# new-display.net
KiCad netlist of a schematic drawn in EAGLE
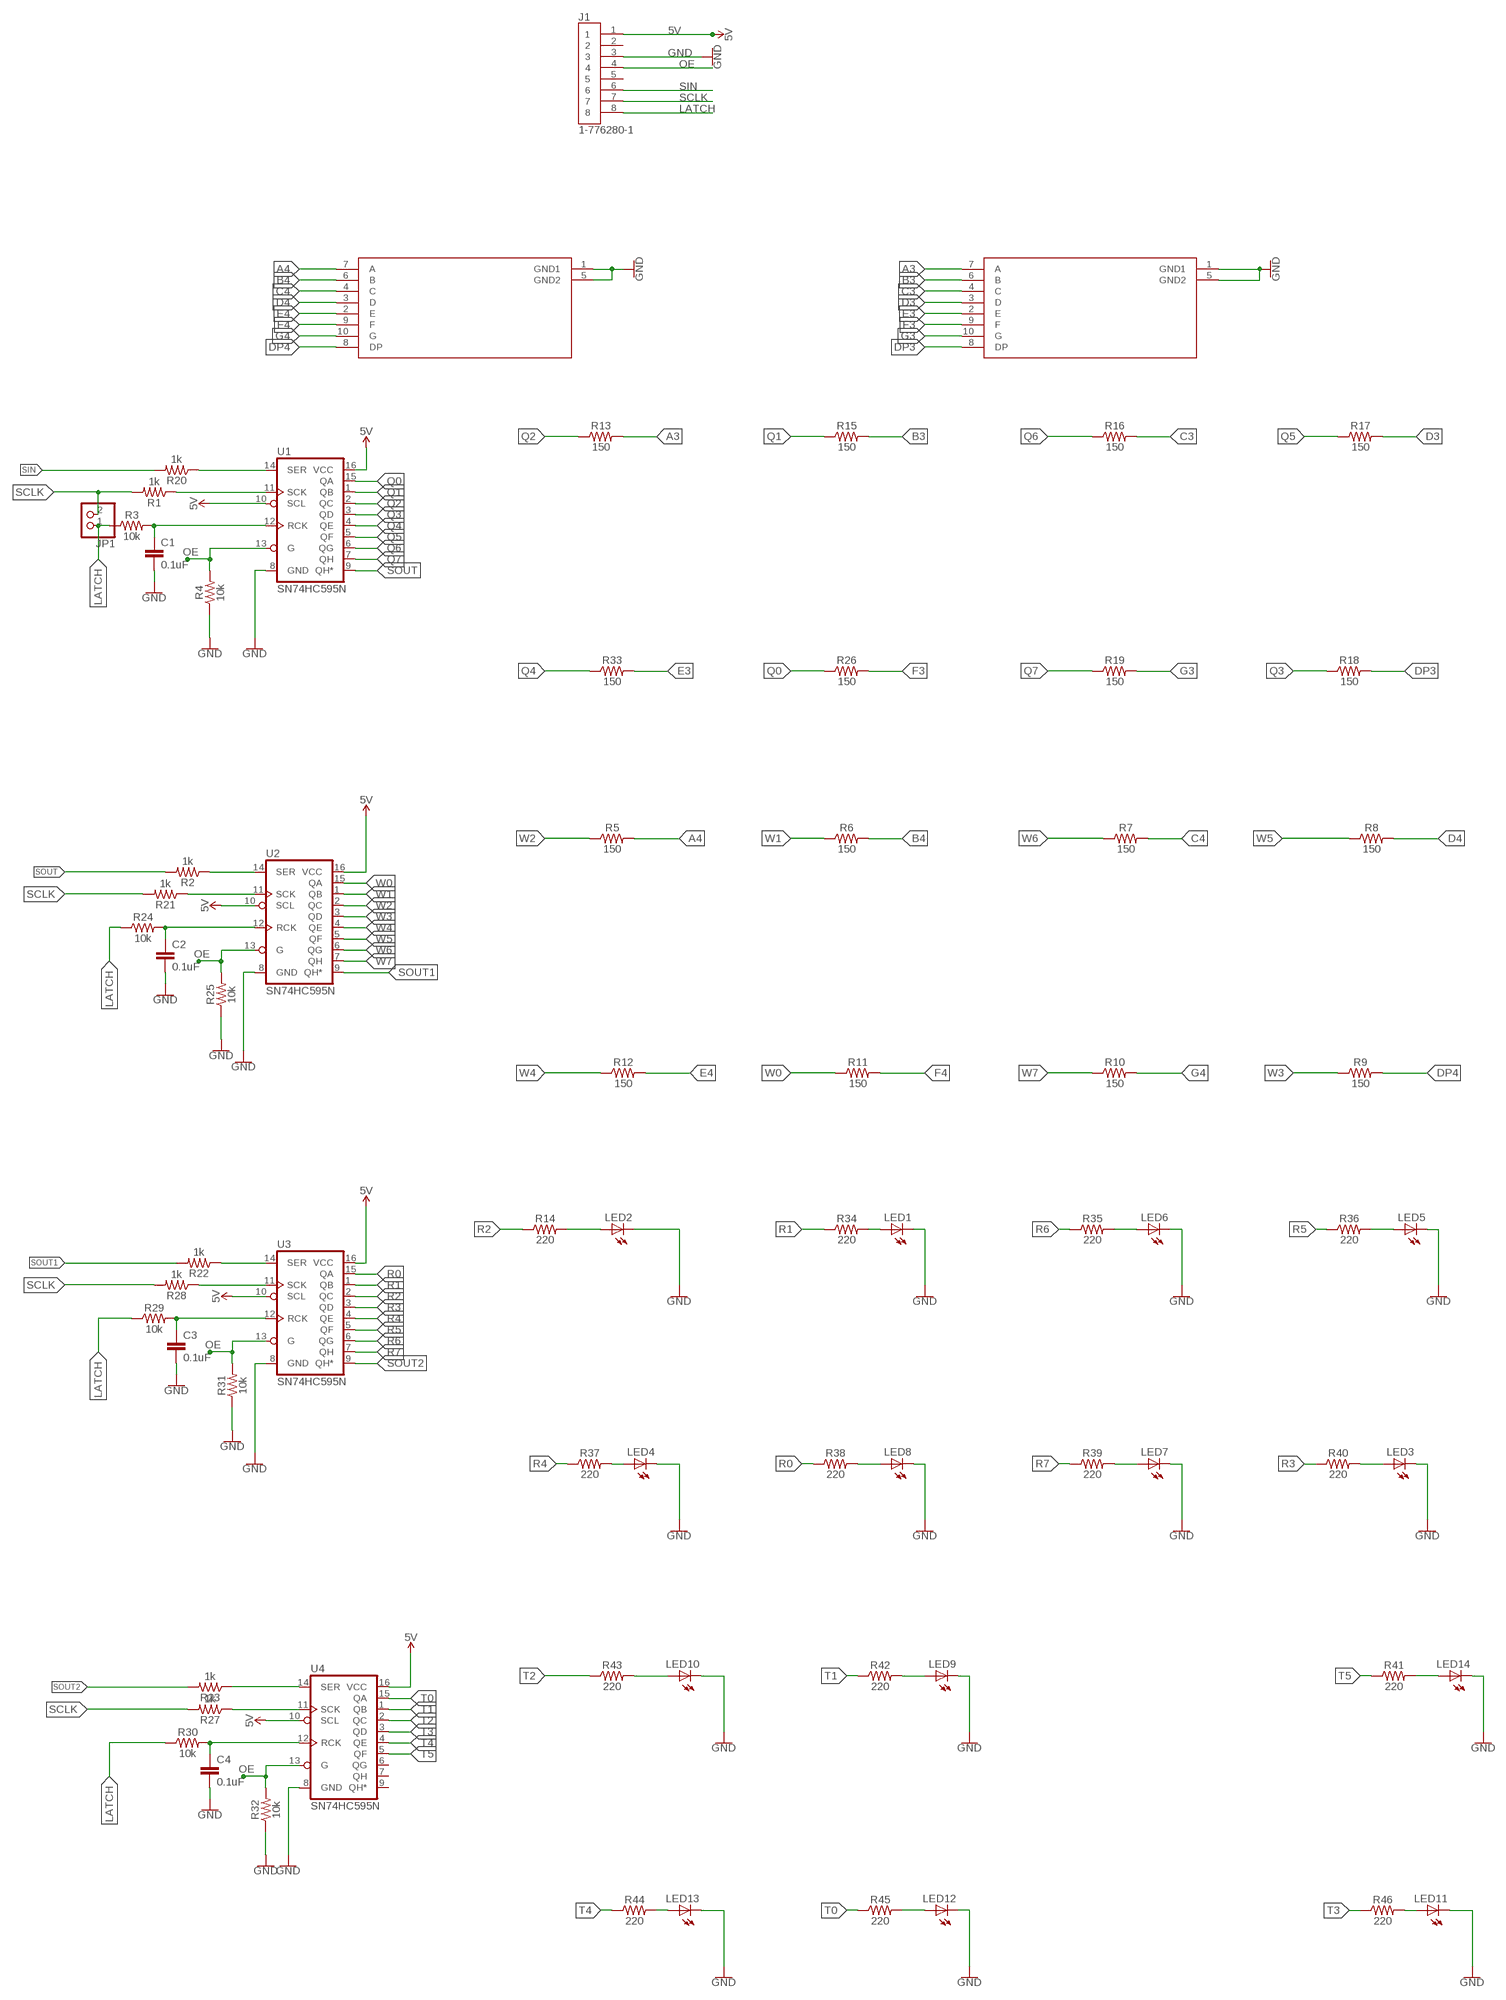
[diagram p0: schematic, sheet 1]

(export (version "E")
  (design (tool "Eeschema 10.0.6"))
  (components
    (comp (ref "C1")
      (value "0.1uF")
      (footprint "eagle-import:CAP-PTH-2.54")
      (libsource (lib "eagle-import") (part "22PF-PTH-2.54MM-200V-5%"))
    )
    (comp (ref "C2")
      (value "0.1uF")
      (footprint "eagle-import:CAP-PTH-2.54")
      (libsource (lib "eagle-import") (part "22PF-PTH-2.54MM-200V-5%"))
    )
    (comp (ref "C3")
      (value "0.1uF")
      (footprint "eagle-import:CAP-PTH-2.54")
      (libsource (lib "eagle-import") (part "22PF-PTH-2.54MM-200V-5%"))
    )
    (comp (ref "C4")
      (value "0.1uF")
      (footprint "eagle-import:CAP-PTH-2.54")
      (libsource (lib "eagle-import") (part "22PF-PTH-2.54MM-200V-5%"))
    )
    (comp (ref "J1")
      (value "1-776280-1")
      (footprint "eagle-import:TE_1-776280-1")
      (fields (field (name "MANUFACTURER") "TE Connectivity"))
      (libsource (lib "eagle-import") (part "1-776280-1"))
    )
    (comp (ref "JP1")
      (value "PINHD-1X2")
      (footprint "eagle-import:1X02")
      (libsource (lib "eagle-import") (part "PINHD-1X2"))
    )
    (comp (ref "LED1")
      (value "LED5MM")
      (footprint "eagle-import:LED5MM")
      (libsource (lib "eagle-import") (part "LED5MM"))
    )
    (comp (ref "LED2")
      (value "LED5MM")
      (footprint "eagle-import:LED5MM")
      (libsource (lib "eagle-import") (part "LED5MM"))
    )
    (comp (ref "LED3")
      (value "LED5MM")
      (footprint "eagle-import:LED5MM")
      (libsource (lib "eagle-import") (part "LED5MM"))
    )
    (comp (ref "LED4")
      (value "LED5MM")
      (footprint "eagle-import:LED5MM")
      (libsource (lib "eagle-import") (part "LED5MM"))
    )
    (comp (ref "LED5")
      (value "LED5MM")
      (footprint "eagle-import:LED5MM")
      (libsource (lib "eagle-import") (part "LED5MM"))
    )
    (comp (ref "LED6")
      (value "LED5MM")
      (footprint "eagle-import:LED5MM")
      (libsource (lib "eagle-import") (part "LED5MM"))
    )
    (comp (ref "LED7")
      (value "LED5MM")
      (footprint "eagle-import:LED5MM")
      (libsource (lib "eagle-import") (part "LED5MM"))
    )
    (comp (ref "LED8")
      (value "LED5MM")
      (footprint "eagle-import:LED5MM")
      (libsource (lib "eagle-import") (part "LED5MM"))
    )
    (comp (ref "LED9")
      (value "LED5MM")
      (footprint "eagle-import:LED5MM")
      (libsource (lib "eagle-import") (part "LED5MM"))
    )
    (comp (ref "LED10")
      (value "LED5MM")
      (footprint "eagle-import:LED5MM")
      (libsource (lib "eagle-import") (part "LED5MM"))
    )
    (comp (ref "LED11")
      (value "LED5MM")
      (footprint "eagle-import:LED5MM")
      (libsource (lib "eagle-import") (part "LED5MM"))
    )
    (comp (ref "LED12")
      (value "LED5MM")
      (footprint "eagle-import:LED5MM")
      (libsource (lib "eagle-import") (part "LED5MM"))
    )
    (comp (ref "LED13")
      (value "LED5MM")
      (footprint "eagle-import:LED5MM")
      (libsource (lib "eagle-import") (part "LED5MM"))
    )
    (comp (ref "LED14")
      (value "LED5MM")
      (footprint "eagle-import:LED5MM")
      (libsource (lib "eagle-import") (part "LED5MM"))
    )
    (comp (ref "R1")
      (value "1k")
      (footprint "eagle-import:AXIAL-0.3")
      (libsource (lib "eagle-import") (part "1KOHM-HORIZ-1/4W-5%"))
    )
    (comp (ref "R2")
      (value "1k")
      (footprint "eagle-import:AXIAL-0.3")
      (libsource (lib "eagle-import") (part "1KOHM-HORIZ-1/4W-5%"))
    )
    (comp (ref "R3")
      (value "10k")
      (footprint "eagle-import:AXIAL-0.3")
      (libsource (lib "eagle-import") (part "10KOHM-HORIZ-1/4W-5%"))
    )
    (comp (ref "R4")
      (value "10k")
      (footprint "eagle-import:AXIAL-0.3")
      (libsource (lib "eagle-import") (part "10KOHM-HORIZ-1/4W-5%"))
    )
    (comp (ref "R5")
      (value "150")
      (footprint "eagle-import:AXIAL-0.3")
      (libsource (lib "eagle-import") (part "10KOHM-HORIZ-1/4W-5%"))
    )
    (comp (ref "R6")
      (value "150")
      (footprint "eagle-import:AXIAL-0.3")
      (libsource (lib "eagle-import") (part "10KOHM-HORIZ-1/4W-5%"))
    )
    (comp (ref "R7")
      (value "150")
      (footprint "eagle-import:AXIAL-0.3")
      (libsource (lib "eagle-import") (part "10KOHM-HORIZ-1/4W-5%"))
    )
    (comp (ref "R8")
      (value "150")
      (footprint "eagle-import:AXIAL-0.3")
      (libsource (lib "eagle-import") (part "10KOHM-HORIZ-1/4W-5%"))
    )
    (comp (ref "R9")
      (value "150")
      (footprint "eagle-import:AXIAL-0.3")
      (libsource (lib "eagle-import") (part "10KOHM-HORIZ-1/4W-5%"))
    )
    (comp (ref "R10")
      (value "150")
      (footprint "eagle-import:AXIAL-0.3")
      (libsource (lib "eagle-import") (part "10KOHM-HORIZ-1/4W-5%"))
    )
    (comp (ref "R11")
      (value "150")
      (footprint "eagle-import:AXIAL-0.3")
      (libsource (lib "eagle-import") (part "10KOHM-HORIZ-1/4W-5%"))
    )
    (comp (ref "R12")
      (value "150")
      (footprint "eagle-import:AXIAL-0.3")
      (libsource (lib "eagle-import") (part "10KOHM-HORIZ-1/4W-5%"))
    )
    (comp (ref "R13")
      (value "150")
      (footprint "eagle-import:AXIAL-0.3")
      (libsource (lib "eagle-import") (part "10KOHM-HORIZ-1/4W-5%"))
    )
    (comp (ref "R14")
      (value "220")
      (footprint "eagle-import:AXIAL-0.3")
      (libsource (lib "eagle-import") (part "10KOHM-HORIZ-1/4W-5%"))
    )
    (comp (ref "R15")
      (value "150")
      (footprint "eagle-import:AXIAL-0.3")
      (libsource (lib "eagle-import") (part "10KOHM-HORIZ-1/4W-5%"))
    )
    (comp (ref "R16")
      (value "150")
      (footprint "eagle-import:AXIAL-0.3")
      (libsource (lib "eagle-import") (part "10KOHM-HORIZ-1/4W-5%"))
    )
    (comp (ref "R17")
      (value "150")
      (footprint "eagle-import:AXIAL-0.3")
      (libsource (lib "eagle-import") (part "10KOHM-HORIZ-1/4W-5%"))
    )
    (comp (ref "R18")
      (value "150")
      (footprint "eagle-import:AXIAL-0.3")
      (libsource (lib "eagle-import") (part "10KOHM-HORIZ-1/4W-5%"))
    )
    (comp (ref "R19")
      (value "150")
      (footprint "eagle-import:AXIAL-0.3")
      (libsource (lib "eagle-import") (part "10KOHM-HORIZ-1/4W-5%"))
    )
    (comp (ref "R20")
      (value "1k")
      (footprint "eagle-import:AXIAL-0.3")
      (libsource (lib "eagle-import") (part "1KOHM-HORIZ-1/4W-5%"))
    )
    (comp (ref "R21")
      (value "1k")
      (footprint "eagle-import:AXIAL-0.3")
      (libsource (lib "eagle-import") (part "1KOHM-HORIZ-1/4W-5%"))
    )
    (comp (ref "R22")
      (value "1k")
      (footprint "eagle-import:AXIAL-0.3")
      (libsource (lib "eagle-import") (part "1KOHM-HORIZ-1/4W-5%"))
    )
    (comp (ref "R23")
      (value "1k")
      (footprint "eagle-import:AXIAL-0.3")
      (libsource (lib "eagle-import") (part "1KOHM-HORIZ-1/4W-5%"))
    )
    (comp (ref "R24")
      (value "10k")
      (footprint "eagle-import:AXIAL-0.3")
      (libsource (lib "eagle-import") (part "10KOHM-HORIZ-1/4W-5%"))
    )
    (comp (ref "R25")
      (value "10k")
      (footprint "eagle-import:AXIAL-0.3")
      (libsource (lib "eagle-import") (part "10KOHM-HORIZ-1/4W-5%"))
    )
    (comp (ref "R26")
      (value "150")
      (footprint "eagle-import:AXIAL-0.3")
      (libsource (lib "eagle-import") (part "10KOHM-HORIZ-1/4W-5%"))
    )
    (comp (ref "R27")
      (value "1k")
      (footprint "eagle-import:AXIAL-0.3")
      (libsource (lib "eagle-import") (part "1KOHM-HORIZ-1/4W-5%"))
    )
    (comp (ref "R28")
      (value "1k")
      (footprint "eagle-import:AXIAL-0.3")
      (libsource (lib "eagle-import") (part "1KOHM-HORIZ-1/4W-5%"))
    )
    (comp (ref "R29")
      (value "10k")
      (footprint "eagle-import:AXIAL-0.3")
      (libsource (lib "eagle-import") (part "10KOHM-HORIZ-1/4W-5%"))
    )
    (comp (ref "R30")
      (value "10k")
      (footprint "eagle-import:AXIAL-0.3")
      (libsource (lib "eagle-import") (part "10KOHM-HORIZ-1/4W-5%"))
    )
    (comp (ref "R31")
      (value "10k")
      (footprint "eagle-import:AXIAL-0.3")
      (libsource (lib "eagle-import") (part "10KOHM-HORIZ-1/4W-5%"))
    )
    (comp (ref "R32")
      (value "10k")
      (footprint "eagle-import:AXIAL-0.3")
      (libsource (lib "eagle-import") (part "10KOHM-HORIZ-1/4W-5%"))
    )
    (comp (ref "R33")
      (value "150")
      (footprint "eagle-import:AXIAL-0.3")
      (libsource (lib "eagle-import") (part "10KOHM-HORIZ-1/4W-5%"))
    )
    (comp (ref "R34")
      (value "220")
      (footprint "eagle-import:AXIAL-0.3")
      (libsource (lib "eagle-import") (part "10KOHM-HORIZ-1/4W-5%"))
    )
    (comp (ref "R35")
      (value "220")
      (footprint "eagle-import:AXIAL-0.3")
      (libsource (lib "eagle-import") (part "10KOHM-HORIZ-1/4W-5%"))
    )
    (comp (ref "R36")
      (value "220")
      (footprint "eagle-import:AXIAL-0.3")
      (libsource (lib "eagle-import") (part "10KOHM-HORIZ-1/4W-5%"))
    )
    (comp (ref "R37")
      (value "220")
      (footprint "eagle-import:AXIAL-0.3")
      (libsource (lib "eagle-import") (part "10KOHM-HORIZ-1/4W-5%"))
    )
    (comp (ref "R38")
      (value "220")
      (footprint "eagle-import:AXIAL-0.3")
      (libsource (lib "eagle-import") (part "10KOHM-HORIZ-1/4W-5%"))
    )
    (comp (ref "R39")
      (value "220")
      (footprint "eagle-import:AXIAL-0.3")
      (libsource (lib "eagle-import") (part "10KOHM-HORIZ-1/4W-5%"))
    )
    (comp (ref "R40")
      (value "220")
      (footprint "eagle-import:AXIAL-0.3")
      (libsource (lib "eagle-import") (part "10KOHM-HORIZ-1/4W-5%"))
    )
    (comp (ref "R41")
      (value "220")
      (footprint "eagle-import:AXIAL-0.3")
      (libsource (lib "eagle-import") (part "10KOHM-HORIZ-1/4W-5%"))
    )
    (comp (ref "R42")
      (value "220")
      (footprint "eagle-import:AXIAL-0.3")
      (libsource (lib "eagle-import") (part "10KOHM-HORIZ-1/4W-5%"))
    )
    (comp (ref "R43")
      (value "220")
      (footprint "eagle-import:AXIAL-0.3")
      (libsource (lib "eagle-import") (part "10KOHM-HORIZ-1/4W-5%"))
    )
    (comp (ref "R44")
      (value "220")
      (footprint "eagle-import:AXIAL-0.3")
      (libsource (lib "eagle-import") (part "10KOHM-HORIZ-1/4W-5%"))
    )
    (comp (ref "R45")
      (value "220")
      (footprint "eagle-import:AXIAL-0.3")
      (libsource (lib "eagle-import") (part "10KOHM-HORIZ-1/4W-5%"))
    )
    (comp (ref "R46")
      (value "220")
      (footprint "eagle-import:AXIAL-0.3")
      (libsource (lib "eagle-import") (part "10KOHM-HORIZ-1/4W-5%"))
    )
    (comp (ref "U$1")
      (value "DISPLAY1.2")
      (footprint "eagle-import:1.2INCH")
      (libsource (lib "eagle-import") (part "DISPLAY1.2"))
    )
    (comp (ref "U$2")
      (value "DISPLAY1.2")
      (footprint "eagle-import:1.2INCH")
      (libsource (lib "eagle-import") (part "DISPLAY1.2"))
    )
    (comp (ref "U1")
      (value "SN74HC595N")
      (footprint "eagle-import:DIP16")
      (libsource (lib "eagle-import") (part "74595NHC"))
    )
    (comp (ref "U2")
      (value "SN74HC595N")
      (footprint "eagle-import:DIP16")
      (libsource (lib "eagle-import") (part "74595NHC"))
    )
    (comp (ref "U3")
      (value "SN74HC595N")
      (footprint "eagle-import:DIP16")
      (libsource (lib "eagle-import") (part "74595NHC"))
    )
    (comp (ref "U4")
      (value "SN74HC595N")
      (footprint "eagle-import:DIP16")
      (libsource (lib "eagle-import") (part "74595NHC"))
    )
  )
  (nets
    (net (code "1") (name "/OE") (class "Default")
      (node (ref "J1") (pin "4") (pinfunction "4_4") (pintype "passive"))
      (node (ref "R25") (pin "P$2") (pinfunction "2_P$2") (pintype "passive"))
      (node (ref "R31") (pin "P$2") (pinfunction "2_P$2") (pintype "passive"))
      (node (ref "R32") (pin "P$2") (pinfunction "2_P$2") (pintype "passive"))
      (node (ref "R4") (pin "P$2") (pinfunction "2_P$2") (pintype "passive"))
      (node (ref "U1") (pin "13") (pinfunction "G_13") (pintype "input"))
      (node (ref "U2") (pin "13") (pinfunction "G_13") (pintype "input"))
      (node (ref "U3") (pin "13") (pinfunction "G_13") (pintype "input"))
      (node (ref "U4") (pin "13") (pinfunction "G_13") (pintype "input"))
    )
    (net (code "2") (name "5V") (class "Default")
      (node (ref "J1") (pin "1") (pinfunction "1_1") (pintype "passive"))
      (node (ref "U1") (pin "10") (pinfunction "SCL_10") (pintype "input"))
      (node (ref "U1") (pin "16") (pinfunction "VCC_16") (pintype "power_in"))
      (node (ref "U2") (pin "10") (pinfunction "SCL_10") (pintype "input"))
      (node (ref "U2") (pin "16") (pinfunction "VCC_16") (pintype "power_in"))
      (node (ref "U3") (pin "10") (pinfunction "SCL_10") (pintype "input"))
      (node (ref "U3") (pin "16") (pinfunction "VCC_16") (pintype "power_in"))
      (node (ref "U4") (pin "10") (pinfunction "SCL_10") (pintype "input"))
      (node (ref "U4") (pin "16") (pinfunction "VCC_16") (pintype "power_in"))
    )
    (net (code "3") (name "A3") (class "Default")
      (node (ref "R13") (pin "P$2") (pinfunction "2_P$2") (pintype "passive"))
      (node (ref "U$1") (pin "7") (pinfunction "A_7") (pintype "bidirectional"))
    )
    (net (code "4") (name "A4") (class "Default")
      (node (ref "R5") (pin "P$2") (pinfunction "2_P$2") (pintype "passive"))
      (node (ref "U$2") (pin "7") (pinfunction "A_7") (pintype "bidirectional"))
    )
    (net (code "5") (name "B3") (class "Default")
      (node (ref "R15") (pin "P$2") (pinfunction "2_P$2") (pintype "passive"))
      (node (ref "U$1") (pin "6") (pinfunction "B_6") (pintype "bidirectional"))
    )
    (net (code "6") (name "B4") (class "Default")
      (node (ref "R6") (pin "P$2") (pinfunction "2_P$2") (pintype "passive"))
      (node (ref "U$2") (pin "6") (pinfunction "B_6") (pintype "bidirectional"))
    )
    (net (code "7") (name "C3") (class "Default")
      (node (ref "R16") (pin "P$2") (pinfunction "2_P$2") (pintype "passive"))
      (node (ref "U$1") (pin "4") (pinfunction "C_4") (pintype "bidirectional"))
    )
    (net (code "8") (name "C4") (class "Default")
      (node (ref "R7") (pin "P$2") (pinfunction "2_P$2") (pintype "passive"))
      (node (ref "U$2") (pin "4") (pinfunction "C_4") (pintype "bidirectional"))
    )
    (net (code "9") (name "D3") (class "Default")
      (node (ref "R17") (pin "P$2") (pinfunction "2_P$2") (pintype "passive"))
      (node (ref "U$1") (pin "3") (pinfunction "D_3") (pintype "bidirectional"))
    )
    (net (code "10") (name "D4") (class "Default")
      (node (ref "R8") (pin "P$2") (pinfunction "2_P$2") (pintype "passive"))
      (node (ref "U$2") (pin "3") (pinfunction "D_3") (pintype "bidirectional"))
    )
    (net (code "11") (name "DP3") (class "Default")
      (node (ref "R18") (pin "P$2") (pinfunction "2_P$2") (pintype "passive"))
      (node (ref "U$1") (pin "8") (pinfunction "DP_8") (pintype "bidirectional"))
    )
    (net (code "12") (name "DP4") (class "Default")
      (node (ref "R9") (pin "P$2") (pinfunction "2_P$2") (pintype "passive"))
      (node (ref "U$2") (pin "8") (pinfunction "DP_8") (pintype "bidirectional"))
    )
    (net (code "13") (name "E3") (class "Default")
      (node (ref "R33") (pin "P$2") (pinfunction "2_P$2") (pintype "passive"))
      (node (ref "U$1") (pin "2") (pinfunction "E_2") (pintype "bidirectional"))
    )
    (net (code "14") (name "E4") (class "Default")
      (node (ref "R12") (pin "P$2") (pinfunction "2_P$2") (pintype "passive"))
      (node (ref "U$2") (pin "2") (pinfunction "E_2") (pintype "bidirectional"))
    )
    (net (code "15") (name "F3") (class "Default")
      (node (ref "R26") (pin "P$2") (pinfunction "2_P$2") (pintype "passive"))
      (node (ref "U$1") (pin "9") (pinfunction "F_9") (pintype "bidirectional"))
    )
    (net (code "16") (name "F4") (class "Default")
      (node (ref "R11") (pin "P$2") (pinfunction "2_P$2") (pintype "passive"))
      (node (ref "U$2") (pin "9") (pinfunction "F_9") (pintype "bidirectional"))
    )
    (net (code "17") (name "G3") (class "Default")
      (node (ref "R19") (pin "P$2") (pinfunction "2_P$2") (pintype "passive"))
      (node (ref "U$1") (pin "10") (pinfunction "G_10") (pintype "bidirectional"))
    )
    (net (code "18") (name "G4") (class "Default")
      (node (ref "R10") (pin "P$2") (pinfunction "2_P$2") (pintype "passive"))
      (node (ref "U$2") (pin "10") (pinfunction "G_10") (pintype "bidirectional"))
    )
    (net (code "19") (name "GND") (class "Default")
      (node (ref "C1") (pin "2") (pinfunction "2_2") (pintype "passive"))
      (node (ref "C2") (pin "2") (pinfunction "2_2") (pintype "passive"))
      (node (ref "C3") (pin "2") (pinfunction "2_2") (pintype "passive"))
      (node (ref "C4") (pin "2") (pinfunction "2_2") (pintype "passive"))
      (node (ref "J1") (pin "3") (pinfunction "3_3") (pintype "passive"))
      (node (ref "LED1") (pin "K") (pinfunction "C_K") (pintype "passive"))
      (node (ref "LED10") (pin "K") (pinfunction "C_K") (pintype "passive"))
      (node (ref "LED11") (pin "K") (pinfunction "C_K") (pintype "passive"))
      (node (ref "LED12") (pin "K") (pinfunction "C_K") (pintype "passive"))
      (node (ref "LED13") (pin "K") (pinfunction "C_K") (pintype "passive"))
      (node (ref "LED14") (pin "K") (pinfunction "C_K") (pintype "passive"))
      (node (ref "LED2") (pin "K") (pinfunction "C_K") (pintype "passive"))
      (node (ref "LED3") (pin "K") (pinfunction "C_K") (pintype "passive"))
      (node (ref "LED4") (pin "K") (pinfunction "C_K") (pintype "passive"))
      (node (ref "LED5") (pin "K") (pinfunction "C_K") (pintype "passive"))
      (node (ref "LED6") (pin "K") (pinfunction "C_K") (pintype "passive"))
      (node (ref "LED7") (pin "K") (pinfunction "C_K") (pintype "passive"))
      (node (ref "LED8") (pin "K") (pinfunction "C_K") (pintype "passive"))
      (node (ref "LED9") (pin "K") (pinfunction "C_K") (pintype "passive"))
      (node (ref "R25") (pin "P$1") (pinfunction "1_P$1") (pintype "passive"))
      (node (ref "R31") (pin "P$1") (pinfunction "1_P$1") (pintype "passive"))
      (node (ref "R32") (pin "P$1") (pinfunction "1_P$1") (pintype "passive"))
      (node (ref "R4") (pin "P$1") (pinfunction "1_P$1") (pintype "passive"))
      (node (ref "U$1") (pin "1") (pinfunction "GND1_1") (pintype "bidirectional"))
      (node (ref "U$1") (pin "5") (pinfunction "GND2_5") (pintype "bidirectional"))
      (node (ref "U$2") (pin "1") (pinfunction "GND1_1") (pintype "bidirectional"))
      (node (ref "U$2") (pin "5") (pinfunction "GND2_5") (pintype "bidirectional"))
      (node (ref "U1") (pin "8") (pinfunction "GND_8") (pintype "power_in"))
      (node (ref "U2") (pin "8") (pinfunction "GND_8") (pintype "power_in"))
      (node (ref "U3") (pin "8") (pinfunction "GND_8") (pintype "power_in"))
      (node (ref "U4") (pin "8") (pinfunction "GND_8") (pintype "power_in"))
    )
    (net (code "20") (name "LATCH") (class "Default")
      (node (ref "J1") (pin "8") (pinfunction "8_8") (pintype "passive"))
      (node (ref "JP1") (pin "1") (pinfunction "1_1") (pintype "passive"))
      (node (ref "R24") (pin "P$1") (pinfunction "1_P$1") (pintype "passive"))
      (node (ref "R29") (pin "P$1") (pinfunction "1_P$1") (pintype "passive"))
      (node (ref "R3") (pin "P$1") (pinfunction "1_P$1") (pintype "passive"))
      (node (ref "R30") (pin "P$1") (pinfunction "1_P$1") (pintype "passive"))
    )
    (net (code "21") (name "Net-(R1-1)") (class "Default")
      (node (ref "R1") (pin "P$1") (pinfunction "1_P$1") (pintype "passive"))
      (node (ref "U1") (pin "11") (pinfunction "SCK_11") (pintype "input"))
    )
    (net (code "22") (name "Net-(R2-1)") (class "Default")
      (node (ref "R2") (pin "P$1") (pinfunction "1_P$1") (pintype "passive"))
      (node (ref "U2") (pin "14") (pinfunction "SER_14") (pintype "input"))
    )
    (net (code "23") (name "Net-(R3-2)") (class "Default")
      (node (ref "C1") (pin "1") (pinfunction "1_1") (pintype "passive"))
      (node (ref "R3") (pin "P$2") (pinfunction "2_P$2") (pintype "passive"))
      (node (ref "U1") (pin "12") (pinfunction "RCK_12") (pintype "input"))
    )
    (net (code "24") (name "Net-(R14-2)") (class "Default")
      (node (ref "LED2") (pin "A") (pinfunction "A_A") (pintype "passive"))
      (node (ref "R14") (pin "P$2") (pinfunction "2_P$2") (pintype "passive"))
    )
    (net (code "25") (name "Net-(R20-1)") (class "Default")
      (node (ref "R20") (pin "P$1") (pinfunction "1_P$1") (pintype "passive"))
      (node (ref "U1") (pin "14") (pinfunction "SER_14") (pintype "input"))
    )
    (net (code "26") (name "Net-(R21-1)") (class "Default")
      (node (ref "R21") (pin "P$1") (pinfunction "1_P$1") (pintype "passive"))
      (node (ref "U2") (pin "11") (pinfunction "SCK_11") (pintype "input"))
    )
    (net (code "27") (name "Net-(R22-1)") (class "Default")
      (node (ref "R22") (pin "P$1") (pinfunction "1_P$1") (pintype "passive"))
      (node (ref "U3") (pin "14") (pinfunction "SER_14") (pintype "input"))
    )
    (net (code "28") (name "Net-(R23-1)") (class "Default")
      (node (ref "R23") (pin "P$1") (pinfunction "1_P$1") (pintype "passive"))
      (node (ref "U4") (pin "14") (pinfunction "SER_14") (pintype "input"))
    )
    (net (code "29") (name "Net-(R24-2)") (class "Default")
      (node (ref "C2") (pin "1") (pinfunction "1_1") (pintype "passive"))
      (node (ref "R24") (pin "P$2") (pinfunction "2_P$2") (pintype "passive"))
      (node (ref "U2") (pin "12") (pinfunction "RCK_12") (pintype "input"))
    )
    (net (code "30") (name "Net-(R27-1)") (class "Default")
      (node (ref "R27") (pin "P$1") (pinfunction "1_P$1") (pintype "passive"))
      (node (ref "U4") (pin "11") (pinfunction "SCK_11") (pintype "input"))
    )
    (net (code "31") (name "Net-(R28-1)") (class "Default")
      (node (ref "R28") (pin "P$1") (pinfunction "1_P$1") (pintype "passive"))
      (node (ref "U3") (pin "11") (pinfunction "SCK_11") (pintype "input"))
    )
    (net (code "32") (name "Net-(R29-2)") (class "Default")
      (node (ref "C3") (pin "1") (pinfunction "1_1") (pintype "passive"))
      (node (ref "R29") (pin "P$2") (pinfunction "2_P$2") (pintype "passive"))
      (node (ref "U3") (pin "12") (pinfunction "RCK_12") (pintype "input"))
    )
    (net (code "33") (name "Net-(R30-2)") (class "Default")
      (node (ref "C4") (pin "1") (pinfunction "1_1") (pintype "passive"))
      (node (ref "R30") (pin "P$2") (pinfunction "2_P$2") (pintype "passive"))
      (node (ref "U4") (pin "12") (pinfunction "RCK_12") (pintype "input"))
    )
    (net (code "34") (name "Net-(R34-2)") (class "Default")
      (node (ref "LED1") (pin "A") (pinfunction "A_A") (pintype "passive"))
      (node (ref "R34") (pin "P$2") (pinfunction "2_P$2") (pintype "passive"))
    )
    (net (code "35") (name "Net-(R35-2)") (class "Default")
      (node (ref "LED6") (pin "A") (pinfunction "A_A") (pintype "passive"))
      (node (ref "R35") (pin "P$2") (pinfunction "2_P$2") (pintype "passive"))
    )
    (net (code "36") (name "Net-(R36-2)") (class "Default")
      (node (ref "LED5") (pin "A") (pinfunction "A_A") (pintype "passive"))
      (node (ref "R36") (pin "P$2") (pinfunction "2_P$2") (pintype "passive"))
    )
    (net (code "37") (name "Net-(R37-2)") (class "Default")
      (node (ref "LED4") (pin "A") (pinfunction "A_A") (pintype "passive"))
      (node (ref "R37") (pin "P$2") (pinfunction "2_P$2") (pintype "passive"))
    )
    (net (code "38") (name "Net-(R38-2)") (class "Default")
      (node (ref "LED8") (pin "A") (pinfunction "A_A") (pintype "passive"))
      (node (ref "R38") (pin "P$2") (pinfunction "2_P$2") (pintype "passive"))
    )
    (net (code "39") (name "Net-(R39-2)") (class "Default")
      (node (ref "LED7") (pin "A") (pinfunction "A_A") (pintype "passive"))
      (node (ref "R39") (pin "P$2") (pinfunction "2_P$2") (pintype "passive"))
    )
    (net (code "40") (name "Net-(R40-2)") (class "Default")
      (node (ref "LED3") (pin "A") (pinfunction "A_A") (pintype "passive"))
      (node (ref "R40") (pin "P$2") (pinfunction "2_P$2") (pintype "passive"))
    )
    (net (code "41") (name "Net-(R41-2)") (class "Default")
      (node (ref "LED14") (pin "A") (pinfunction "A_A") (pintype "passive"))
      (node (ref "R41") (pin "P$2") (pinfunction "2_P$2") (pintype "passive"))
    )
    (net (code "42") (name "Net-(R42-2)") (class "Default")
      (node (ref "LED9") (pin "A") (pinfunction "A_A") (pintype "passive"))
      (node (ref "R42") (pin "P$2") (pinfunction "2_P$2") (pintype "passive"))
    )
    (net (code "43") (name "Net-(R43-2)") (class "Default")
      (node (ref "LED10") (pin "A") (pinfunction "A_A") (pintype "passive"))
      (node (ref "R43") (pin "P$2") (pinfunction "2_P$2") (pintype "passive"))
    )
    (net (code "44") (name "Net-(R44-2)") (class "Default")
      (node (ref "LED13") (pin "A") (pinfunction "A_A") (pintype "passive"))
      (node (ref "R44") (pin "P$2") (pinfunction "2_P$2") (pintype "passive"))
    )
    (net (code "45") (name "Net-(R45-2)") (class "Default")
      (node (ref "LED12") (pin "A") (pinfunction "A_A") (pintype "passive"))
      (node (ref "R45") (pin "P$2") (pinfunction "2_P$2") (pintype "passive"))
    )
    (net (code "46") (name "Net-(R46-2)") (class "Default")
      (node (ref "LED11") (pin "A") (pinfunction "A_A") (pintype "passive"))
      (node (ref "R46") (pin "P$2") (pinfunction "2_P$2") (pintype "passive"))
    )
    (net (code "47") (name "Q0") (class "Default")
      (node (ref "R26") (pin "P$1") (pinfunction "1_P$1") (pintype "passive"))
      (node (ref "U1") (pin "15") (pinfunction "QA_15") (pintype "tri_state"))
    )
    (net (code "48") (name "Q1") (class "Default")
      (node (ref "R15") (pin "P$1") (pinfunction "1_P$1") (pintype "passive"))
      (node (ref "U1") (pin "1") (pinfunction "QB_1") (pintype "tri_state"))
    )
    (net (code "49") (name "Q2") (class "Default")
      (node (ref "R13") (pin "P$1") (pinfunction "1_P$1") (pintype "passive"))
      (node (ref "U1") (pin "2") (pinfunction "QC_2") (pintype "tri_state"))
    )
    (net (code "50") (name "Q3") (class "Default")
      (node (ref "R18") (pin "P$1") (pinfunction "1_P$1") (pintype "passive"))
      (node (ref "U1") (pin "3") (pinfunction "QD_3") (pintype "tri_state"))
    )
    (net (code "51") (name "Q4") (class "Default")
      (node (ref "R33") (pin "P$1") (pinfunction "1_P$1") (pintype "passive"))
      (node (ref "U1") (pin "4") (pinfunction "QE_4") (pintype "tri_state"))
    )
    (net (code "52") (name "Q5") (class "Default")
      (node (ref "R17") (pin "P$1") (pinfunction "1_P$1") (pintype "passive"))
      (node (ref "U1") (pin "5") (pinfunction "QF_5") (pintype "tri_state"))
    )
    (net (code "53") (name "Q6") (class "Default")
      (node (ref "R16") (pin "P$1") (pinfunction "1_P$1") (pintype "passive"))
      (node (ref "U1") (pin "6") (pinfunction "QG_6") (pintype "tri_state"))
    )
    (net (code "54") (name "Q7") (class "Default")
      (node (ref "R19") (pin "P$1") (pinfunction "1_P$1") (pintype "passive"))
      (node (ref "U1") (pin "7") (pinfunction "QH_7") (pintype "tri_state"))
    )
    (net (code "55") (name "R0") (class "Default")
      (node (ref "R38") (pin "P$1") (pinfunction "1_P$1") (pintype "passive"))
      (node (ref "U3") (pin "15") (pinfunction "QA_15") (pintype "tri_state"))
    )
    (net (code "56") (name "R1") (class "Default")
      (node (ref "R34") (pin "P$1") (pinfunction "1_P$1") (pintype "passive"))
      (node (ref "U3") (pin "1") (pinfunction "QB_1") (pintype "tri_state"))
    )
    (net (code "57") (name "R2") (class "Default")
      (node (ref "R14") (pin "P$1") (pinfunction "1_P$1") (pintype "passive"))
      (node (ref "U3") (pin "2") (pinfunction "QC_2") (pintype "tri_state"))
    )
    (net (code "58") (name "R3") (class "Default")
      (node (ref "R40") (pin "P$1") (pinfunction "1_P$1") (pintype "passive"))
      (node (ref "U3") (pin "3") (pinfunction "QD_3") (pintype "tri_state"))
    )
    (net (code "59") (name "R4") (class "Default")
      (node (ref "R37") (pin "P$1") (pinfunction "1_P$1") (pintype "passive"))
      (node (ref "U3") (pin "4") (pinfunction "QE_4") (pintype "tri_state"))
    )
    (net (code "60") (name "R5") (class "Default")
      (node (ref "R36") (pin "P$1") (pinfunction "1_P$1") (pintype "passive"))
      (node (ref "U3") (pin "5") (pinfunction "QF_5") (pintype "tri_state"))
    )
    (net (code "61") (name "R6") (class "Default")
      (node (ref "R35") (pin "P$1") (pinfunction "1_P$1") (pintype "passive"))
      (node (ref "U3") (pin "6") (pinfunction "QG_6") (pintype "tri_state"))
    )
    (net (code "62") (name "R7") (class "Default")
      (node (ref "R39") (pin "P$1") (pinfunction "1_P$1") (pintype "passive"))
      (node (ref "U3") (pin "7") (pinfunction "QH_7") (pintype "tri_state"))
    )
    (net (code "63") (name "SCLK") (class "Default")
      (node (ref "J1") (pin "7") (pinfunction "7_7") (pintype "passive"))
      (node (ref "JP1") (pin "2") (pinfunction "2_2") (pintype "passive"))
      (node (ref "R1") (pin "P$2") (pinfunction "2_P$2") (pintype "passive"))
      (node (ref "R21") (pin "P$2") (pinfunction "2_P$2") (pintype "passive"))
      (node (ref "R27") (pin "P$2") (pinfunction "2_P$2") (pintype "passive"))
      (node (ref "R28") (pin "P$2") (pinfunction "2_P$2") (pintype "passive"))
    )
    (net (code "64") (name "SIN") (class "Default")
      (node (ref "J1") (pin "6") (pinfunction "6_6") (pintype "passive"))
      (node (ref "R20") (pin "P$2") (pinfunction "2_P$2") (pintype "passive"))
    )
    (net (code "65") (name "SOUT") (class "Default")
      (node (ref "R2") (pin "P$2") (pinfunction "2_P$2") (pintype "passive"))
      (node (ref "U1") (pin "9") (pinfunction "QH*_9") (pintype "tri_state"))
    )
    (net (code "66") (name "SOUT1") (class "Default")
      (node (ref "R22") (pin "P$2") (pinfunction "2_P$2") (pintype "passive"))
      (node (ref "U2") (pin "9") (pinfunction "QH*_9") (pintype "tri_state"))
    )
    (net (code "67") (name "SOUT2") (class "Default")
      (node (ref "R23") (pin "P$2") (pinfunction "2_P$2") (pintype "passive"))
      (node (ref "U3") (pin "9") (pinfunction "QH*_9") (pintype "tri_state"))
    )
    (net (code "68") (name "T0") (class "Default")
      (node (ref "R45") (pin "P$1") (pinfunction "1_P$1") (pintype "passive"))
      (node (ref "U4") (pin "15") (pinfunction "QA_15") (pintype "tri_state"))
    )
    (net (code "69") (name "T1") (class "Default")
      (node (ref "R42") (pin "P$1") (pinfunction "1_P$1") (pintype "passive"))
      (node (ref "U4") (pin "1") (pinfunction "QB_1") (pintype "tri_state"))
    )
    (net (code "70") (name "T2") (class "Default")
      (node (ref "R43") (pin "P$1") (pinfunction "1_P$1") (pintype "passive"))
      (node (ref "U4") (pin "2") (pinfunction "QC_2") (pintype "tri_state"))
    )
    (net (code "71") (name "T3") (class "Default")
      (node (ref "R46") (pin "P$1") (pinfunction "1_P$1") (pintype "passive"))
      (node (ref "U4") (pin "3") (pinfunction "QD_3") (pintype "tri_state"))
    )
    (net (code "72") (name "T4") (class "Default")
      (node (ref "R44") (pin "P$1") (pinfunction "1_P$1") (pintype "passive"))
      (node (ref "U4") (pin "4") (pinfunction "QE_4") (pintype "tri_state"))
    )
    (net (code "73") (name "T5") (class "Default")
      (node (ref "R41") (pin "P$1") (pinfunction "1_P$1") (pintype "passive"))
      (node (ref "U4") (pin "5") (pinfunction "QF_5") (pintype "tri_state"))
    )
    (net (code "74") (name "W0") (class "Default")
      (node (ref "R11") (pin "P$1") (pinfunction "1_P$1") (pintype "passive"))
      (node (ref "U2") (pin "15") (pinfunction "QA_15") (pintype "tri_state"))
    )
    (net (code "75") (name "W1") (class "Default")
      (node (ref "R6") (pin "P$1") (pinfunction "1_P$1") (pintype "passive"))
      (node (ref "U2") (pin "1") (pinfunction "QB_1") (pintype "tri_state"))
    )
    (net (code "76") (name "W2") (class "Default")
      (node (ref "R5") (pin "P$1") (pinfunction "1_P$1") (pintype "passive"))
      (node (ref "U2") (pin "2") (pinfunction "QC_2") (pintype "tri_state"))
    )
    (net (code "77") (name "W3") (class "Default")
      (node (ref "R9") (pin "P$1") (pinfunction "1_P$1") (pintype "passive"))
      (node (ref "U2") (pin "3") (pinfunction "QD_3") (pintype "tri_state"))
    )
    (net (code "78") (name "W4") (class "Default")
      (node (ref "R12") (pin "P$1") (pinfunction "1_P$1") (pintype "passive"))
      (node (ref "U2") (pin "4") (pinfunction "QE_4") (pintype "tri_state"))
    )
    (net (code "79") (name "W5") (class "Default")
      (node (ref "R8") (pin "P$1") (pinfunction "1_P$1") (pintype "passive"))
      (node (ref "U2") (pin "5") (pinfunction "QF_5") (pintype "tri_state"))
    )
    (net (code "80") (name "W6") (class "Default")
      (node (ref "R7") (pin "P$1") (pinfunction "1_P$1") (pintype "passive"))
      (node (ref "U2") (pin "6") (pinfunction "QG_6") (pintype "tri_state"))
    )
    (net (code "81") (name "W7") (class "Default")
      (node (ref "R10") (pin "P$1") (pinfunction "1_P$1") (pintype "passive"))
      (node (ref "U2") (pin "7") (pinfunction "QH_7") (pintype "tri_state"))
    )
    (net (code "82") (name "unconnected-(J1-Pad2)") (class "Default")
      (node (ref "J1") (pin "2") (pinfunction "2_2") (pintype "passive"))
    )
    (net (code "83") (name "unconnected-(J1-Pad5)") (class "Default")
      (node (ref "J1") (pin "5") (pinfunction "5_5") (pintype "passive"))
    )
    (net (code "84") (name "unconnected-(U4-QG-Pad6)") (class "Default")
      (node (ref "U4") (pin "6") (pinfunction "QG_6") (pintype "tri_state"))
    )
    (net (code "85") (name "unconnected-(U4-QH*-Pad9)") (class "Default")
      (node (ref "U4") (pin "9") (pinfunction "QH*_9") (pintype "tri_state"))
    )
    (net (code "86") (name "unconnected-(U4-QH-Pad7)") (class "Default")
      (node (ref "U4") (pin "7") (pinfunction "QH_7") (pintype "tri_state"))
    )
  )
)
